# TBA820-Module-KOSMOS.net
KiCad netlist of a schematic drawn in EAGLE
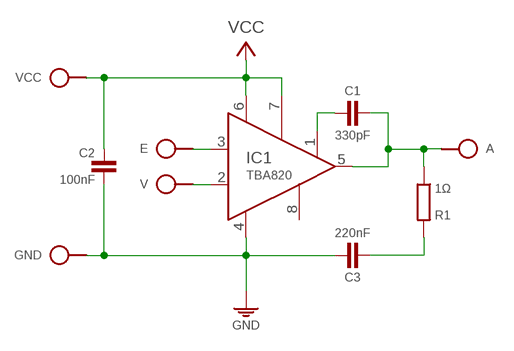
[diagram p0: schematic, sheet 1]

(export (version "E")
  (design (tool "Eeschema 10.0.6"))
  (components
    (comp (ref "A")
      (value "SPAD")
      (footprint "eagle-import:SPAD")
      (libsource (lib "eagle-import") (part "SPAD"))
    )
    (comp (ref "C1")
      (value "330pF")
      (footprint "eagle-import:C050-020X044")
      (libsource (lib "eagle-import") (part "C-H050-020X044"))
    )
    (comp (ref "C2")
      (value "100nF")
      (footprint "eagle-import:C075-035X050")
      (libsource (lib "eagle-import") (part "C075-035X050"))
    )
    (comp (ref "C3")
      (value "220nF")
      (footprint "eagle-import:C050-020X044")
      (libsource (lib "eagle-import") (part "C-H050-020X044"))
    )
    (comp (ref "E")
      (value "SPAD")
      (footprint "eagle-import:SPAD")
      (libsource (lib "eagle-import") (part "SPAD"))
    )
    (comp (ref "GND")
      (value "SPAD")
      (footprint "eagle-import:SPAD")
      (libsource (lib "eagle-import") (part "SPAD"))
    )
    (comp (ref "IC1")
      (value "TBA820")
      (footprint "eagle-import:DIL08")
      (libsource (lib "eagle-import") (part "TBA820"))
    )
    (comp (ref "R1")
      (value "1Ω")
      (footprint "eagle-import:0204_10")
      (libsource (lib "eagle-import") (part "R0204/10"))
    )
    (comp (ref "V")
      (value "SPAD")
      (footprint "eagle-import:SPAD")
      (libsource (lib "eagle-import") (part "SPAD"))
    )
    (comp (ref "VCC")
      (value "SPAD")
      (footprint "eagle-import:SPAD")
      (libsource (lib "eagle-import") (part "SPAD"))
    )
  )
  (nets
    (net (code "1") (name "GND") (class "Default")
      (node (ref "C2") (pin "2") (pinfunction "2_2") (pintype "passive"))
      (node (ref "C3") (pin "2") (pinfunction "2_2") (pintype "passive"))
      (node (ref "GND") (pin "1") (pinfunction "P$1_1") (pintype "passive"))
      (node (ref "IC1") (pin "4") (pinfunction "GND_4") (pintype "power_in"))
    )
    (net (code "2") (name "Net-(A-P$1)") (class "Default")
      (node (ref "A") (pin "1") (pinfunction "P$1_1") (pintype "passive"))
      (node (ref "C1") (pin "2") (pinfunction "2_2") (pintype "passive"))
      (node (ref "IC1") (pin "5") (pinfunction "OUT_5") (pintype "output"))
      (node (ref "R1") (pin "2") (pinfunction "1_2") (pintype "passive"))
    )
    (net (code "3") (name "Net-(E-P$1)") (class "Default")
      (node (ref "E") (pin "1") (pinfunction "P$1_1") (pintype "passive"))
      (node (ref "IC1") (pin "3") (pinfunction "INPUT_3") (pintype "input"))
    )
    (net (code "4") (name "Net-(IC1-FREQ)") (class "Default")
      (node (ref "C1") (pin "1") (pinfunction "1_1") (pintype "passive"))
      (node (ref "IC1") (pin "1") (pinfunction "FREQ_1") (pintype "input"))
    )
    (net (code "5") (name "Net-(IC1-GAIN)") (class "Default")
      (node (ref "IC1") (pin "2") (pinfunction "GAIN_2") (pintype "input"))
      (node (ref "V") (pin "1") (pinfunction "P$1_1") (pintype "passive"))
    )
    (net (code "6") (name "Net-(R1-2)") (class "Default")
      (node (ref "C3") (pin "1") (pinfunction "1_1") (pintype "passive"))
      (node (ref "R1") (pin "1") (pinfunction "2_1") (pintype "passive"))
    )
    (net (code "7") (name "VCC") (class "Default")
      (node (ref "C2") (pin "1") (pinfunction "1_1") (pintype "passive"))
      (node (ref "IC1") (pin "6") (pinfunction "VCC_6") (pintype "power_in"))
      (node (ref "IC1") (pin "7") (pinfunction "BOOT_7") (pintype "input"))
      (node (ref "VCC") (pin "1") (pinfunction "P$1_1") (pintype "passive"))
    )
    (net (code "8") (name "unconnected-(IC1-RIPPLE-Pad8)") (class "Default")
      (node (ref "IC1") (pin "8") (pinfunction "RIPPLE_8") (pintype "input"))
    )
  )
)
